# Buck-SCH.net
KiCad netlist of a schematic drawn in Altium Designer
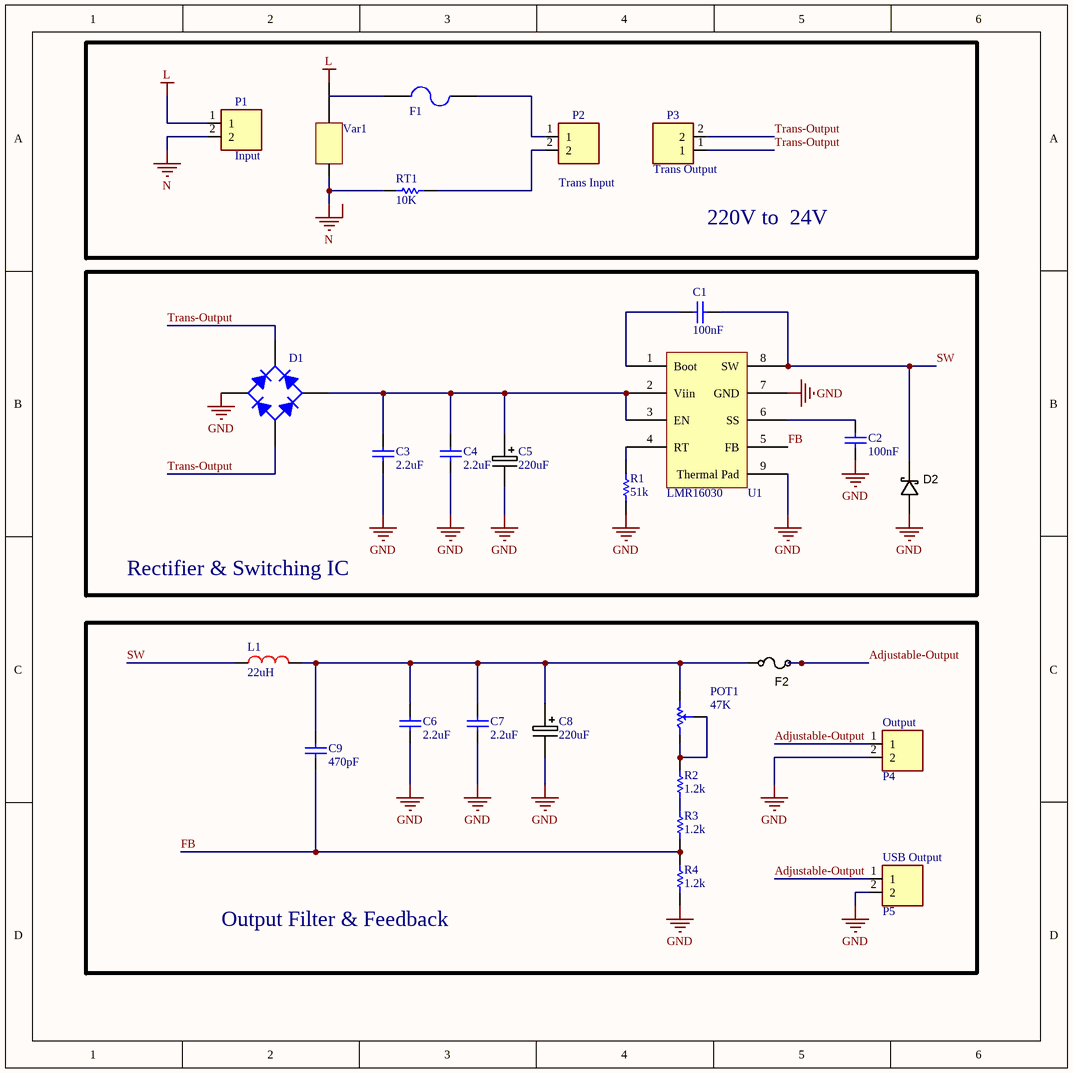
[diagram p0: Buck-SCH.SchDoc]

(export (version "E")
  (design (tool "Eeschema 10.0.6"))
  (components
    (comp (ref "C1")
      (value "100nF")
      (footprint "CAP0603")
      (description "100nF-0603")
      (fields (field (name "DESIGNER") "Abbas Basereh"))
      (libsource (lib "Altium") (part "CAP SMD PACKAGE"))
    )
    (comp (ref "C2")
      (value "100nF")
      (footprint "CAP0603")
      (description "100nF-0603")
      (fields (field (name "DESIGNER") "Abbas Basereh"))
      (libsource (lib "Altium") (part "CAP SMD PACKAGE"))
    )
    (comp (ref "C3")
      (value "2.2uF")
      (footprint "CAP0805")
      (description "2.2UF-0805")
      (fields (field (name "DESIGNER") "Abbas Basereh"))
      (libsource (lib "Altium") (part "CAP SMD PACKAGE"))
    )
    (comp (ref "C4")
      (value "2.2uF")
      (footprint "CAP0805")
      (description "2.2UF-0805")
      (fields (field (name "DESIGNER") "Abbas Basereh"))
      (libsource (lib "Altium") (part "CAP SMD PACKAGE"))
    )
    (comp (ref "C5")
      (value "220uF")
      (footprint "PANACAP-F-GENERIC")
      (description "220uF-63V")
      (libsource (lib "vh_altium_library") (part "PANACAP-47UF-63V-FK"))
    )
    (comp (ref "C6")
      (value "2.2uF")
      (footprint "CAP0805")
      (description "2.2UF-0805")
      (fields (field (name "DESIGNER") "Abbas Basereh"))
      (libsource (lib "Altium") (part "CAP SMD PACKAGE"))
    )
    (comp (ref "C7")
      (value "2.2uF")
      (footprint "CAP0805")
      (description "2.2UF-0805")
      (fields (field (name "DESIGNER") "Abbas Basereh"))
      (libsource (lib "Altium") (part "CAP SMD PACKAGE"))
    )
    (comp (ref "C8")
      (value "220uF")
      (footprint "PANACAP-F-GENERIC")
      (description "220uF-63V")
      (libsource (lib "vh_altium_library") (part "PANACAP-47UF-63V-FK"))
    )
    (comp (ref "C9")
      (value "470pF")
      (footprint "CAP0603")
      (description "470pF-0603")
      (fields (field (name "DESIGNER") "Abbas Basereh"))
      (libsource (lib "Altium") (part "CAP SMD PACKAGE"))
    )
    (comp (ref "D1")
      (value "Diode Bridge")
      (footprint "Bridge KBU PACKAGE")
      (description "Full Wave Diode Bridge")
      (fields (field (name "DESIGNER") "Abbas Basereh"))
      (libsource (lib "Altium") (part "Diode Bridge TOTAL SIZE"))
    )
    (comp (ref "D2")
      (value "schottky diode")
      (footprint "DO-214AB")
      (description "Diode Schottky SMD 40V 3A SMC")
      (libsource (lib "Utiliti_Library") (part "DIODE_SCHOTTKY_30BQ100TRPBF"))
    )
    (comp (ref "F1")
      (value "F=1.0 A")
      (footprint "Fuse 5x20 With holder pin")
      (description "Fuses 5x20")
      (fields (field (name "DESIGNER") "Abbas Basereh"))
      (libsource (lib "Altium") (part "Fuse 5x20 with holdeer pins"))
    )
    (comp (ref "F2")
      (value "Slow-blow")
      (footprint "RESC3216X70N")
      (description "Fuse 4A 1206 SMD")
      (libsource (lib "Utiliti_Library") (part "FUSE_160mA_1206"))
    )
    (comp (ref "L1") (value "22uH") (footprint "Inductor") (libsource (lib "Inductor") (part "Inductor")))
    (comp (ref "P1")
      (value "Input")
      (footprint "MSTBF_2")
      (description "Power Terminal 2pin,Header, 2-Pin")
      (libsource (lib "5.08mm") (part "CONN_PWL_2"))
    )
    (comp (ref "P2")
      (value "Trans Input")
      (footprint "MSTBF_2")
      (description "Power Terminal 2pin,Header, 2-Pin")
      (libsource (lib "5.08mm") (part "CONN_PWL_2"))
    )
    (comp (ref "P3")
      (value "Trans Output")
      (footprint "MSTBF_2")
      (description "Power Terminal 2pin,Header, 2-Pin")
      (libsource (lib "") (part "CONN_PWL_2_1"))
    )
    (comp (ref "P4")
      (value "Output")
      (footprint "MSTBF_2")
      (description "Power Terminal 2pin,Header, 2-Pin")
      (libsource (lib "5.08mm") (part "CONN_PWL_2"))
    )
    (comp (ref "P5")
      (value "USB Output")
      (footprint "MSTBF_2")
      (description "Power Terminal 2pin,Header, 2-Pin")
      (libsource (lib "5.08mm") (part "CONN_PWL_2"))
    )
    (comp (ref "POT1")
      (value "47K")
      (footprint "POT")
      (description "POT-47K")
      (libsource (lib "Altium") (part "POT"))
    )
    (comp (ref "R1")
      (value "51k")
      (footprint "RESC3413X04N")
      (description "51K-0805")
      (fields (field (name "DESIGNER") "Abbas Basereh"))
      (libsource (lib "Altium") (part "RES 0805 0.125W"))
    )
    (comp (ref "R2")
      (value "1.2k")
      (footprint "RESC3413X04N")
      (description "1.2k-0805")
      (fields (field (name "DESIGNER") "Abbas Basereh"))
      (libsource (lib "Altium") (part "RES 0805 0.125W"))
    )
    (comp (ref "R3")
      (value "1.2k")
      (footprint "RESC3413X04N")
      (description "1.2k-0805")
      (fields (field (name "DESIGNER") "Abbas Basereh"))
      (libsource (lib "Altium") (part "RES 0805 0.125W"))
    )
    (comp (ref "R4")
      (value "1.2k")
      (footprint "RESC3413X04N")
      (description "1.2k-0805")
      (fields (field (name "DESIGNER") "Abbas Basereh"))
      (libsource (lib "Altium") (part "RES 0805 0.125W"))
    )
    (comp (ref "RT1")
      (value "10K")
      (footprint "RES0402")
      (description "NTC 10K 0402")
      (fields (field (name "DESIGNER") "Abbas Basereh"))
      (libsource (lib "Altium") (part "RES SMD PACKAGE"))
    )
    (comp (ref "U1") (value "LMR16030") (footprint "U?") (libsource (lib "LMR16030") (part "LMR16030")))
    (comp (ref "Var1")
      (value "Varistor")
      (footprint "Varistor")
      (libsource (lib "Varistor") (part "Varistor"))
    )
  )
  (nets
    (net (code "1") (name "/Adjustable-Output") (class "Default")
      (node (ref "F2") (pin "2") (pinfunction "2_2") (pintype "passive"))
      (node (ref "P4") (pin "1") (pinfunction "1_1") (pintype "passive"))
      (node (ref "P5") (pin "1") (pinfunction "1_1") (pintype "passive"))
    )
    (net (code "2") (name "/FB") (class "Default")
      (node (ref "C9") (pin "1") (pinfunction "1_1") (pintype "passive"))
      (node (ref "R3") (pin "1") (pinfunction "1_1") (pintype "passive"))
      (node (ref "R4") (pin "2") (pinfunction "2_2") (pintype "passive"))
      (node (ref "U1") (pin "5") (pinfunction "FB_5") (pintype "passive"))
    )
    (net (code "3") (name "/SW") (class "Default")
      (node (ref "C1") (pin "1") (pinfunction "1_1") (pintype "passive"))
      (node (ref "D2") (pin "K") (pinfunction "K_K") (pintype "passive"))
      (node (ref "U1") (pin "8") (pinfunction "SW_8") (pintype "passive"))
    )
    (net (code "4") (name "/Trans-Output") (class "Default")
      (node (ref "D1") (pin "1") (pinfunction "+_1") (pintype "passive"))
      (node (ref "D1") (pin "4") (pinfunction "-_4") (pintype "passive"))
      (node (ref "P3") (pin "1") (pinfunction "1_1") (pintype "passive"))
      (node (ref "P3") (pin "2") (pinfunction "2_2") (pintype "passive"))
    )
    (net (code "5") (name "GND") (class "Default")
      (node (ref "C2") (pin "1") (pinfunction "1_1") (pintype "passive"))
      (node (ref "C3") (pin "1") (pinfunction "1_1") (pintype "passive"))
      (node (ref "C4") (pin "1") (pinfunction "1_1") (pintype "passive"))
      (node (ref "C5") (pin "-") (pinfunction "-_-") (pintype "passive"))
      (node (ref "C6") (pin "1") (pinfunction "1_1") (pintype "passive"))
      (node (ref "C7") (pin "1") (pinfunction "1_1") (pintype "passive"))
      (node (ref "C8") (pin "-") (pinfunction "-_-") (pintype "passive"))
      (node (ref "D1") (pin "2") (pinfunction "AC_2") (pintype "passive"))
      (node (ref "D2") (pin "A") (pinfunction "A_A") (pintype "passive"))
      (node (ref "P4") (pin "2") (pinfunction "2_2") (pintype "passive"))
      (node (ref "P5") (pin "2") (pinfunction "2_2") (pintype "passive"))
      (node (ref "R1") (pin "1") (pinfunction "1_1") (pintype "passive"))
      (node (ref "R4") (pin "1") (pinfunction "1_1") (pintype "passive"))
      (node (ref "U1") (pin "7") (pinfunction "GND_7") (pintype "passive"))
      (node (ref "U1") (pin "9") (pinfunction "Thermal_Pad_9") (pintype "passive"))
    )
    (net (code "6") (name "L") (class "Default")
      (node (ref "P1") (pin "1") (pinfunction "1_1") (pintype "passive"))
    )
    (net (code "7") (name "N") (class "Default")
      (node (ref "P1") (pin "2") (pinfunction "2_2") (pintype "passive"))
      (node (ref "RT1") (pin "1") (pinfunction "1_1") (pintype "passive"))
    )
    (net (code "8") (name "Net-(F1-Pad2)") (class "Default")
      (node (ref "F1") (pin "2") (pinfunction "2_2") (pintype "passive"))
      (node (ref "P2") (pin "1") (pinfunction "1_1") (pintype "passive"))
    )
    (net (code "9") (name "Net-(P2-Pad2)") (class "Default")
      (node (ref "P2") (pin "2") (pinfunction "2_2") (pintype "passive"))
      (node (ref "RT1") (pin "2") (pinfunction "2_2") (pintype "passive"))
    )
    (net (code "10") (name "Net-(POT1-CCW)") (class "Default")
      (node (ref "POT1") (pin "1") (pinfunction "CCW_1") (pintype "passive"))
      (node (ref "POT1") (pin "3") (pinfunction "SetPoint_3") (pintype "passive"))
      (node (ref "R2") (pin "2") (pinfunction "2_2") (pintype "passive"))
    )
    (net (code "11") (name "Net-(POT1-CW)") (class "Default")
      (node (ref "C6") (pin "2") (pinfunction "2_2") (pintype "passive"))
      (node (ref "C7") (pin "2") (pinfunction "2_2") (pintype "passive"))
      (node (ref "C8") (pin "+") (pinfunction "+_+") (pintype "passive"))
      (node (ref "C9") (pin "2") (pinfunction "2_2") (pintype "passive"))
      (node (ref "F2") (pin "1") (pinfunction "1_1") (pintype "passive"))
      (node (ref "POT1") (pin "2") (pinfunction "CW_2") (pintype "passive"))
    )
    (net (code "12") (name "Net-(R2-Pad1)") (class "Default")
      (node (ref "R2") (pin "1") (pinfunction "1_1") (pintype "passive"))
      (node (ref "R3") (pin "2") (pinfunction "2_2") (pintype "passive"))
    )
    (net (code "13") (name "Net-(U1-Boot)") (class "Default")
      (node (ref "C1") (pin "2") (pinfunction "2_2") (pintype "passive"))
      (node (ref "U1") (pin "1") (pinfunction "Boot_1") (pintype "passive"))
    )
    (net (code "14") (name "Net-(U1-EN)") (class "Default")
      (node (ref "C3") (pin "2") (pinfunction "2_2") (pintype "passive"))
      (node (ref "C4") (pin "2") (pinfunction "2_2") (pintype "passive"))
      (node (ref "C5") (pin "+") (pinfunction "+_+") (pintype "passive"))
      (node (ref "D1") (pin "3") (pinfunction "AC_3") (pintype "passive"))
      (node (ref "U1") (pin "2") (pinfunction "Viin_2") (pintype "passive"))
      (node (ref "U1") (pin "3") (pinfunction "EN_3") (pintype "passive"))
    )
    (net (code "15") (name "Net-(U1-RT)") (class "Default")
      (node (ref "R1") (pin "2") (pinfunction "2_2") (pintype "passive"))
      (node (ref "U1") (pin "4") (pinfunction "RT_4") (pintype "passive"))
    )
    (net (code "16") (name "Net-(U1-SS)") (class "Default")
      (node (ref "C2") (pin "2") (pinfunction "2_2") (pintype "passive"))
      (node (ref "U1") (pin "6") (pinfunction "SS_6") (pintype "passive"))
    )
    (net (code "17") (name "unconnected-(F1-Pad1)") (class "Default")
      (node (ref "F1") (pin "1") (pinfunction "1_1") (pintype "passive"))
    )
    (net (code "18") (name "unconnected-(L1-Pad1)") (class "Default")
      (node (ref "L1") (pin "1") (pinfunction "1_1") (pintype "passive"))
    )
    (net (code "19") (name "unconnected-(L1-Pad2)") (class "Default")
      (node (ref "L1") (pin "2") (pinfunction "2_2") (pintype "passive"))
    )
    (net (code "20") (name "unconnected-(Var1-Pad1)") (class "Default")
      (node (ref "Var1") (pin "1") (pinfunction "1_1") (pintype "passive"))
    )
    (net (code "21") (name "unconnected-(Var1-Pad2)") (class "Default")
      (node (ref "Var1") (pin "2") (pinfunction "2_2") (pintype "passive"))
    )
  )
)
